# Part_K.net
KiCad netlist of a schematic drawn in Altium Designer
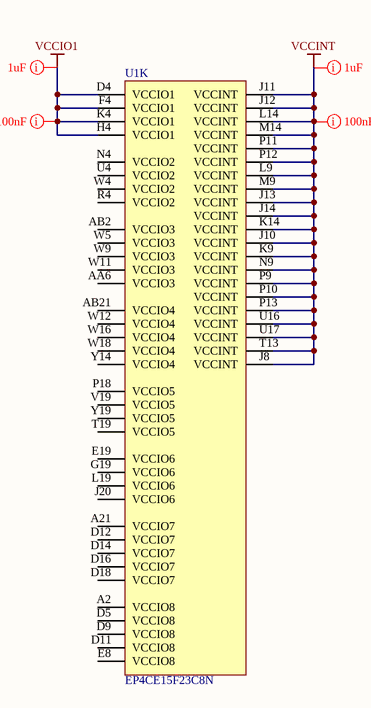
[diagram p0: Part K.SchDoc]

(export (version "E")
  (design (tool "Eeschema 10.0.6"))
  (components
    (comp (ref "U1")
      (value "EP4CE15F23C8N")
      (footprint "FBGA484_A-240")
      (fields (field (name "MANUFACTURER") "Altera"))
      (libsource (lib "Schlib1") (part "FPGA_EP4CE15F23C8N"))
    )
  )
  (nets
    (net (code "1") (name "VCCINT") (class "Default")
      (node (ref "U1") (pin "J10") (pinfunction "VCCINT_J10") (pintype "power_in"))
      (node (ref "U1") (pin "J11") (pinfunction "VCCINT_J11") (pintype "power_in"))
      (node (ref "U1") (pin "J12") (pinfunction "VCCINT_J12") (pintype "power_in"))
      (node (ref "U1") (pin "J13") (pinfunction "VCCINT_J13") (pintype "power_in"))
      (node (ref "U1") (pin "J14") (pinfunction "VCCINT_J14") (pintype "power_in"))
      (node (ref "U1") (pin "J8") (pinfunction "VCCINT_J8") (pintype "power_in"))
      (node (ref "U1") (pin "K14") (pinfunction "VCCINT_K14") (pintype "power_in"))
      (node (ref "U1") (pin "K9") (pinfunction "VCCINT_K9") (pintype "power_in"))
      (node (ref "U1") (pin "L14") (pinfunction "VCCINT_L14") (pintype "power_in"))
      (node (ref "U1") (pin "L9") (pinfunction "VCCINT_L9") (pintype "power_in"))
      (node (ref "U1") (pin "M14") (pinfunction "VCCINT_M14") (pintype "power_in"))
      (node (ref "U1") (pin "M9") (pinfunction "VCCINT_M9") (pintype "power_in"))
      (node (ref "U1") (pin "N9") (pinfunction "VCCINT_N9") (pintype "power_in"))
      (node (ref "U1") (pin "P10") (pinfunction "VCCINT_P10") (pintype "power_in"))
      (node (ref "U1") (pin "P11") (pinfunction "VCCINT_P11") (pintype "power_in"))
      (node (ref "U1") (pin "P12") (pinfunction "VCCINT_P12") (pintype "power_in"))
      (node (ref "U1") (pin "P13") (pinfunction "VCCINT_P13") (pintype "power_in"))
      (node (ref "U1") (pin "P9") (pinfunction "VCCINT_P9") (pintype "power_in"))
      (node (ref "U1") (pin "T13") (pinfunction "VCCINT_T13") (pintype "power_in"))
      (node (ref "U1") (pin "U16") (pinfunction "VCCINT_U16") (pintype "power_in"))
      (node (ref "U1") (pin "U17") (pinfunction "VCCINT_U17") (pintype "power_in"))
    )
    (net (code "2") (name "VCCIO1") (class "Default")
      (node (ref "U1") (pin "D4") (pinfunction "VCCIO1_D4") (pintype "power_in"))
      (node (ref "U1") (pin "F4") (pinfunction "VCCIO1_F4") (pintype "power_in"))
      (node (ref "U1") (pin "H4") (pinfunction "VCCIO1_H4") (pintype "power_in"))
      (node (ref "U1") (pin "K4") (pinfunction "VCCIO1_K4") (pintype "power_in"))
    )
    (net (code "3") (name "unconnected-(U1K-VCCIO2-PadN4)") (class "Default")
      (node (ref "U1") (pin "N4") (pinfunction "VCCIO2_N4") (pintype "power_in"))
    )
    (net (code "4") (name "unconnected-(U1K-VCCIO2-PadR4)") (class "Default")
      (node (ref "U1") (pin "R4") (pinfunction "VCCIO2_R4") (pintype "power_in"))
    )
    (net (code "5") (name "unconnected-(U1K-VCCIO2-PadU4)") (class "Default")
      (node (ref "U1") (pin "U4") (pinfunction "VCCIO2_U4") (pintype "power_in"))
    )
    (net (code "6") (name "unconnected-(U1K-VCCIO2-PadW4)") (class "Default")
      (node (ref "U1") (pin "W4") (pinfunction "VCCIO2_W4") (pintype "power_in"))
    )
    (net (code "7") (name "unconnected-(U1K-VCCIO3-PadAA6)") (class "Default")
      (node (ref "U1") (pin "AA6") (pinfunction "VCCIO3_AA6") (pintype "power_in"))
    )
    (net (code "8") (name "unconnected-(U1K-VCCIO3-PadAB2)") (class "Default")
      (node (ref "U1") (pin "AB2") (pinfunction "VCCIO3_AB2") (pintype "power_in"))
    )
    (net (code "9") (name "unconnected-(U1K-VCCIO3-PadW5)") (class "Default")
      (node (ref "U1") (pin "W5") (pinfunction "VCCIO3_W5") (pintype "power_in"))
    )
    (net (code "10") (name "unconnected-(U1K-VCCIO3-PadW9)") (class "Default")
      (node (ref "U1") (pin "W9") (pinfunction "VCCIO3_W9") (pintype "power_in"))
    )
    (net (code "11") (name "unconnected-(U1K-VCCIO3-PadW11)") (class "Default")
      (node (ref "U1") (pin "W11") (pinfunction "VCCIO3_W11") (pintype "power_in"))
    )
    (net (code "12") (name "unconnected-(U1K-VCCIO4-PadAB21)") (class "Default")
      (node (ref "U1") (pin "AB21") (pinfunction "VCCIO4_AB21") (pintype "power_in"))
    )
    (net (code "13") (name "unconnected-(U1K-VCCIO4-PadW12)") (class "Default")
      (node (ref "U1") (pin "W12") (pinfunction "VCCIO4_W12") (pintype "power_in"))
    )
    (net (code "14") (name "unconnected-(U1K-VCCIO4-PadW16)") (class "Default")
      (node (ref "U1") (pin "W16") (pinfunction "VCCIO4_W16") (pintype "power_in"))
    )
    (net (code "15") (name "unconnected-(U1K-VCCIO4-PadW18)") (class "Default")
      (node (ref "U1") (pin "W18") (pinfunction "VCCIO4_W18") (pintype "power_in"))
    )
    (net (code "16") (name "unconnected-(U1K-VCCIO4-PadY14)") (class "Default")
      (node (ref "U1") (pin "Y14") (pinfunction "VCCIO4_Y14") (pintype "power_in"))
    )
    (net (code "17") (name "unconnected-(U1K-VCCIO5-PadP18)") (class "Default")
      (node (ref "U1") (pin "P18") (pinfunction "VCCIO5_P18") (pintype "power_in"))
    )
    (net (code "18") (name "unconnected-(U1K-VCCIO5-PadT19)") (class "Default")
      (node (ref "U1") (pin "T19") (pinfunction "VCCIO5_T19") (pintype "power_in"))
    )
    (net (code "19") (name "unconnected-(U1K-VCCIO5-PadV19)") (class "Default")
      (node (ref "U1") (pin "V19") (pinfunction "VCCIO5_V19") (pintype "power_in"))
    )
    (net (code "20") (name "unconnected-(U1K-VCCIO5-PadY19)") (class "Default")
      (node (ref "U1") (pin "Y19") (pinfunction "VCCIO5_Y19") (pintype "power_in"))
    )
    (net (code "21") (name "unconnected-(U1K-VCCIO6-PadE19)") (class "Default")
      (node (ref "U1") (pin "E19") (pinfunction "VCCIO6_E19") (pintype "power_in"))
    )
    (net (code "22") (name "unconnected-(U1K-VCCIO6-PadG19)") (class "Default")
      (node (ref "U1") (pin "G19") (pinfunction "VCCIO6_G19") (pintype "power_in"))
    )
    (net (code "23") (name "unconnected-(U1K-VCCIO6-PadJ20)") (class "Default")
      (node (ref "U1") (pin "J20") (pinfunction "VCCIO6_J20") (pintype "power_in"))
    )
    (net (code "24") (name "unconnected-(U1K-VCCIO6-PadL19)") (class "Default")
      (node (ref "U1") (pin "L19") (pinfunction "VCCIO6_L19") (pintype "power_in"))
    )
    (net (code "25") (name "unconnected-(U1K-VCCIO7-PadA21)") (class "Default")
      (node (ref "U1") (pin "A21") (pinfunction "VCCIO7_A21") (pintype "power_in"))
    )
    (net (code "26") (name "unconnected-(U1K-VCCIO7-PadD12)") (class "Default")
      (node (ref "U1") (pin "D12") (pinfunction "VCCIO7_D12") (pintype "power_in"))
    )
    (net (code "27") (name "unconnected-(U1K-VCCIO7-PadD14)") (class "Default")
      (node (ref "U1") (pin "D14") (pinfunction "VCCIO7_D14") (pintype "power_in"))
    )
    (net (code "28") (name "unconnected-(U1K-VCCIO7-PadD16)") (class "Default")
      (node (ref "U1") (pin "D16") (pinfunction "VCCIO7_D16") (pintype "power_in"))
    )
    (net (code "29") (name "unconnected-(U1K-VCCIO7-PadD18)") (class "Default")
      (node (ref "U1") (pin "D18") (pinfunction "VCCIO7_D18") (pintype "power_in"))
    )
    (net (code "30") (name "unconnected-(U1K-VCCIO8-PadA2)") (class "Default")
      (node (ref "U1") (pin "A2") (pinfunction "VCCIO8_A2") (pintype "power_in"))
    )
    (net (code "31") (name "unconnected-(U1K-VCCIO8-PadD5)") (class "Default")
      (node (ref "U1") (pin "D5") (pinfunction "VCCIO8_D5") (pintype "power_in"))
    )
    (net (code "32") (name "unconnected-(U1K-VCCIO8-PadD9)") (class "Default")
      (node (ref "U1") (pin "D9") (pinfunction "VCCIO8_D9") (pintype "power_in"))
    )
    (net (code "33") (name "unconnected-(U1K-VCCIO8-PadD11)") (class "Default")
      (node (ref "U1") (pin "D11") (pinfunction "VCCIO8_D11") (pintype "power_in"))
    )
    (net (code "34") (name "unconnected-(U1K-VCCIO8-PadE8)") (class "Default")
      (node (ref "U1") (pin "E8") (pinfunction "VCCIO8_E8") (pintype "power_in"))
    )
  )
)
